# DSO_Power.net
KiCad netlist of a schematic drawn in Altium Designer
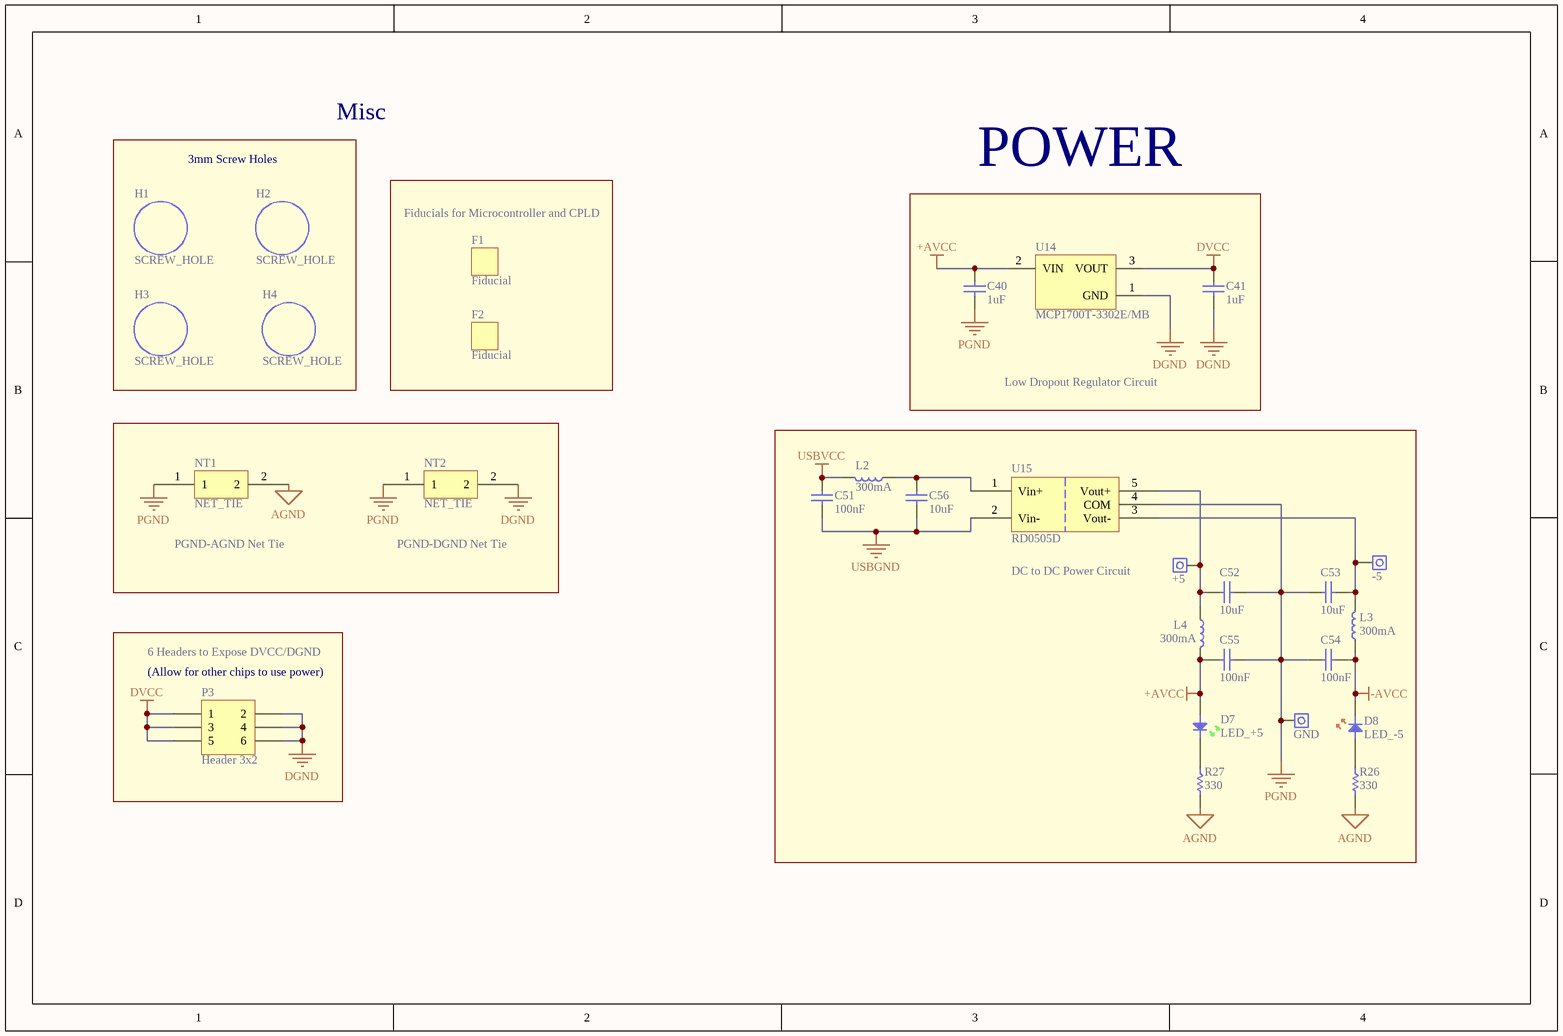
[diagram p0: DSO_Power.SchDoc]

(export (version "E")
  (design (tool "Eeschema 10.0.6"))
  (components
    (comp (ref "C40")
      (value "1uF")
      (footprint "0805C")
      (description "Capacitor")
      (fields (field (name "REVIEWED BY") "RM - 2018/08/05"))
      (libsource (lib "DSO") (part "C"))
    )
    (comp (ref "C41")
      (value "1uF")
      (footprint "0805C")
      (description "Capacitor")
      (fields (field (name "REVIEWED BY") "RM - 2018/08/05"))
      (libsource (lib "DSO") (part "C"))
    )
    (comp (ref "C51")
      (value "100nF")
      (footprint "0805C")
      (description "Capacitor")
      (fields (field (name "REVIEWED BY") "RM - 2018/08/05"))
      (libsource (lib "DSO") (part "C"))
    )
    (comp (ref "C52")
      (value "10uF")
      (footprint "0805C")
      (description "Capacitor")
      (fields (field (name "REVIEWED BY") "RM - 2018/08/05"))
      (libsource (lib "DSO") (part "C"))
    )
    (comp (ref "C53")
      (value "10uF")
      (footprint "0805C")
      (description "Capacitor")
      (fields (field (name "REVIEWED BY") "RM - 2018/08/05"))
      (libsource (lib "DSO") (part "C"))
    )
    (comp (ref "C54")
      (value "100nF")
      (footprint "0805C")
      (description "Capacitor")
      (fields (field (name "REVIEWED BY") "RM - 2018/08/05"))
      (libsource (lib "DSO") (part "C"))
    )
    (comp (ref "C55")
      (value "100nF")
      (footprint "0805C")
      (description "Capacitor")
      (fields (field (name "REVIEWED BY") "RM - 2018/08/05"))
      (libsource (lib "DSO") (part "C"))
    )
    (comp (ref "C56")
      (value "10uF")
      (footprint "0805C")
      (description "Capacitor")
      (fields (field (name "REVIEWED BY") "RM - 2018/08/05"))
      (libsource (lib "DSO") (part "C"))
    )
    (comp (ref "D7")
      (value "LED_+5")
      (footprint "0805D-GREEN")
      (description "Light Emitting Diode")
      (fields (field (name "REVIEWED BY") "RM - 2018/08/05"))
      (libsource (lib "DSO") (part "LED GREEN"))
    )
    (comp (ref "D8")
      (value "LED_-5")
      (footprint "0805D-RED")
      (description "Light Emitting Diode")
      (fields (field (name "REVIEWED BY") "RM - 2018/08/05"))
      (libsource (lib "DSO") (part "LED RED"))
    )
    (comp (ref "F1") (value "Fiducial") (footprint "Fiducial") (libsource (lib "DSO") (part "Fiducial")))
    (comp (ref "F2") (value "Fiducial") (footprint "Fiducial") (libsource (lib "DSO") (part "Fiducial")))
    (comp (ref "H1")
      (value "SCREW_HOLE")
      (footprint "SCREW_HOLE")
      (libsource (lib "DSO") (part "SCREW_HOLE"))
    )
    (comp (ref "H2")
      (value "SCREW_HOLE")
      (footprint "SCREW_HOLE")
      (libsource (lib "DSO") (part "SCREW_HOLE"))
    )
    (comp (ref "H3")
      (value "SCREW_HOLE")
      (footprint "SCREW_HOLE")
      (libsource (lib "DSO") (part "SCREW_HOLE"))
    )
    (comp (ref "H4")
      (value "SCREW_HOLE")
      (footprint "SCREW_HOLE")
      (libsource (lib "DSO") (part "SCREW_HOLE"))
    )
    (comp (ref "L2")
      (value "300mA")
      (footprint "0805")
      (description "Inductor")
      (fields (field (name "REVIEWED BY") "RM - 2018/08/05"))
      (libsource (lib "DSO") (part "I"))
    )
    (comp (ref "L3")
      (value "300mA")
      (footprint "0805")
      (description "Inductor")
      (fields (field (name "REVIEWED BY") "RM - 2018/08/05"))
      (libsource (lib "DSO") (part "I"))
    )
    (comp (ref "L4")
      (value "300mA")
      (footprint "0805")
      (description "Inductor")
      (fields (field (name "REVIEWED BY") "RM - 2018/08/05"))
      (libsource (lib "DSO") (part "I"))
    )
    (comp (ref "NT1")
      (value "NET_TIE")
      (footprint "NET_TIE")
      (description "Net Tie")
      (libsource (lib "DSO") (part "NET_TIE"))
    )
    (comp (ref "NT2")
      (value "NET_TIE")
      (footprint "NET_TIE")
      (description "Net Tie")
      (libsource (lib "DSO") (part "NET_TIE"))
    )
    (comp (ref "P3")
      (value "Header 3x2")
      (footprint "HDR3x2")
      (description "Header, 5-Pin")
      (fields (field (name "REVIEWED BY") "RM - 2018/08/05"))
      (libsource (lib "DSO") (part "Header 3x2"))
    )
    (comp (ref "R26")
      (value "330")
      (footprint "0805")
      (description "Resistor")
      (fields (field (name "REVIEWED BY") "RM - 2018/08/05"))
      (libsource (lib "DSO") (part "R"))
    )
    (comp (ref "R27")
      (value "330")
      (footprint "0805")
      (description "Resistor")
      (fields (field (name "REVIEWED BY") "RM - 2018/08/05"))
      (libsource (lib "DSO") (part "R"))
    )
    (comp (ref "TP9")
      (value "-5")
      (footprint "PIN 1.8mm")
      (description "Pad")
      (libsource (lib "DSO") (part "WIRE"))
    )
    (comp (ref "TP10")
      (value "GND")
      (footprint "PIN 1.8mm")
      (description "Pad")
      (libsource (lib "DSO") (part "WIRE"))
    )
    (comp (ref "TP11")
      (value "+5")
      (footprint "PIN 1.8mm")
      (description "Pad")
      (libsource (lib "DSO") (part "WIRE"))
    )
    (comp (ref "U14")
      (value "MCP1700T-3302E/MB")
      (footprint "SOT89")
      (description "Low Quiescent Current LDO, 3-Pin SOT-89, Extended Temperature, Tape and Reel")
      (fields (field (name "REVIEWED BY") "RM - 2018/08/05"))
      (libsource (lib "DSO") (part "MCP1700T"))
    )
    (comp (ref "U15")
      (value "RD0505D")
      (footprint "SIP_NMG")
      (description "(ADV) DC to DC converter 5V in +-5V out")
      (fields (field (name "REVIEWED BY") "RM - 2018/08/05"))
      (libsource (lib "DSO") (part "RD0505D"))
    )
  )
  (nets
    (net (code "1") (name "+AVCC") (class "Default")
      (node (ref "C40") (pin "1") (pinfunction "1_1") (pintype "passive"))
      (node (ref "C55") (pin "1") (pinfunction "1_1") (pintype "passive"))
      (node (ref "D7") (pin "A") (pinfunction "A_A") (pintype "passive"))
      (node (ref "L4") (pin "2") (pinfunction "2_2") (pintype "passive"))
      (node (ref "U14") (pin "2") (pinfunction "VIN_2") (pintype "power_in"))
    )
    (net (code "2") (name "-AVCC") (class "Default")
      (node (ref "C54") (pin "1") (pinfunction "1_1") (pintype "passive"))
      (node (ref "D8") (pin "K") (pinfunction "K_K") (pintype "passive"))
      (node (ref "L3") (pin "1") (pinfunction "1_1") (pintype "passive"))
    )
    (net (code "3") (name "AGND") (class "Default")
      (node (ref "NT1") (pin "2") (pinfunction "2_2") (pintype "passive"))
      (node (ref "R26") (pin "2") (pintype "passive"))
      (node (ref "R27") (pin "2") (pintype "passive"))
    )
    (net (code "4") (name "DGND") (class "Default")
      (node (ref "C41") (pin "2") (pinfunction "2_2") (pintype "passive"))
      (node (ref "NT2") (pin "2") (pinfunction "2_2") (pintype "passive"))
      (node (ref "P3") (pin "2") (pinfunction "2_2") (pintype "passive"))
      (node (ref "P3") (pin "4") (pinfunction "4_4") (pintype "passive"))
      (node (ref "P3") (pin "6") (pinfunction "6_6") (pintype "passive"))
      (node (ref "U14") (pin "1") (pinfunction "GND_1") (pintype "power_in"))
    )
    (net (code "5") (name "DVCC") (class "Default")
      (node (ref "C41") (pin "1") (pinfunction "1_1") (pintype "passive"))
      (node (ref "P3") (pin "1") (pinfunction "1_1") (pintype "passive"))
      (node (ref "P3") (pin "3") (pinfunction "3_3") (pintype "passive"))
      (node (ref "P3") (pin "5") (pinfunction "5_5") (pintype "passive"))
      (node (ref "U14") (pin "3") (pinfunction "VOUT_3") (pintype "power_in"))
    )
    (net (code "6") (name "Net-(D7-PadK)") (class "Default")
      (node (ref "D7") (pin "K") (pinfunction "K_K") (pintype "passive"))
      (node (ref "R27") (pin "1") (pintype "passive"))
    )
    (net (code "7") (name "Net-(D8-PadA)") (class "Default")
      (node (ref "D8") (pin "A") (pinfunction "A_A") (pintype "passive"))
      (node (ref "R26") (pin "1") (pintype "passive"))
    )
    (net (code "8") (name "Net-(U15-Vin+)") (class "Default")
      (node (ref "C56") (pin "1") (pinfunction "1_1") (pintype "passive"))
      (node (ref "L2") (pin "1") (pinfunction "1_1") (pintype "passive"))
      (node (ref "U15") (pin "1") (pinfunction "Vin+_1") (pintype "passive"))
    )
    (net (code "9") (name "Net-(U15-Vout+)") (class "Default")
      (node (ref "C52") (pin "1") (pinfunction "1_1") (pintype "passive"))
      (node (ref "L4") (pin "1") (pinfunction "1_1") (pintype "passive"))
      (node (ref "TP11") (pin "1") (pintype "passive"))
      (node (ref "U15") (pin "5") (pinfunction "Vout+_5") (pintype "passive"))
    )
    (net (code "10") (name "Net-(U15-Vout-)") (class "Default")
      (node (ref "C53") (pin "1") (pinfunction "1_1") (pintype "passive"))
      (node (ref "L3") (pin "2") (pinfunction "2_2") (pintype "passive"))
      (node (ref "TP9") (pin "1") (pintype "passive"))
      (node (ref "U15") (pin "3") (pinfunction "Vout-_3") (pintype "passive"))
    )
    (net (code "11") (name "PGND") (class "Default")
      (node (ref "C40") (pin "2") (pinfunction "2_2") (pintype "passive"))
      (node (ref "C52") (pin "2") (pinfunction "2_2") (pintype "passive"))
      (node (ref "C53") (pin "2") (pinfunction "2_2") (pintype "passive"))
      (node (ref "C54") (pin "2") (pinfunction "2_2") (pintype "passive"))
      (node (ref "C55") (pin "2") (pinfunction "2_2") (pintype "passive"))
      (node (ref "NT1") (pin "1") (pinfunction "1_1") (pintype "passive"))
      (node (ref "NT2") (pin "1") (pinfunction "1_1") (pintype "passive"))
      (node (ref "TP10") (pin "1") (pintype "passive"))
      (node (ref "U15") (pin "4") (pinfunction "COM_4") (pintype "passive"))
    )
    (net (code "12") (name "USBGND") (class "Default")
      (node (ref "C51") (pin "2") (pinfunction "2_2") (pintype "passive"))
      (node (ref "C56") (pin "2") (pinfunction "2_2") (pintype "passive"))
      (node (ref "U15") (pin "2") (pinfunction "Vin-_2") (pintype "passive"))
    )
    (net (code "13") (name "USBVCC") (class "Default")
      (node (ref "C51") (pin "1") (pinfunction "1_1") (pintype "passive"))
      (node (ref "L2") (pin "2") (pinfunction "2_2") (pintype "passive"))
    )
  )
)
